# filter.net
KiCad netlist of a schematic drawn in EAGLE
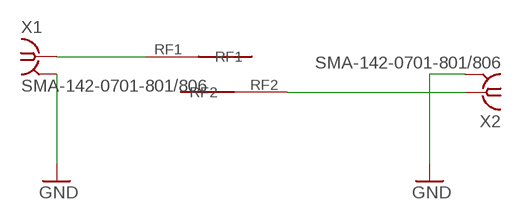
[diagram p0: schematic, sheet 1]

(export (version "E")
  (design (tool "Eeschema 10.0.6"))
  (components
    (comp (ref "U$1")
      (value "FILTER")
      (footprint "eagle-import:RF")
      (libsource (lib "eagle-import") (part "FILTER"))
    )
    (comp (ref "X1")
      (value "SMA-142-0701-801/806")
      (footprint "eagle-import:J502-ND-142-0701-801_806")
      (fields (field (name "MF") "JOHNSON COMPONENTS") (field (name "MPN") "142-0701-801"))
      (libsource (lib "eagle-import") (part "SMA-142-0701-801/806"))
    )
    (comp (ref "X2")
      (value "SMA-142-0701-801/806")
      (footprint "eagle-import:J502-ND-142-0701-801_806")
      (fields (field (name "MF") "JOHNSON COMPONENTS") (field (name "MPN") "142-0701-801"))
      (libsource (lib "eagle-import") (part "SMA-142-0701-801/806"))
    )
  )
  (nets
    (net (code "1") (name "GND") (class "Default")
      (node (ref "X1") (pin "G@1") (pinfunction "2_G@1") (pintype "passive"))
      (node (ref "X1") (pin "G@2") (pinfunction "2_G@2") (pintype "passive"))
      (node (ref "X1") (pin "G@3") (pinfunction "2_G@3") (pintype "passive"))
      (node (ref "X1") (pin "G@4") (pinfunction "2_G@4") (pintype "passive"))
      (node (ref "X2") (pin "G@1") (pinfunction "2_G@1") (pintype "passive"))
      (node (ref "X2") (pin "G@2") (pinfunction "2_G@2") (pintype "passive"))
      (node (ref "X2") (pin "G@3") (pinfunction "2_G@3") (pintype "passive"))
      (node (ref "X2") (pin "G@4") (pinfunction "2_G@4") (pintype "passive"))
    )
    (net (code "2") (name "Net-(U$1-PadRF1)") (class "Default")
      (node (ref "U$1") (pin "RF1") (pinfunction "RF1_RF1") (pintype "bidirectional"))
      (node (ref "X1") (pin "1") (pinfunction "1_1") (pintype "passive"))
    )
    (net (code "3") (name "Net-(U$1-PadRF2)") (class "Default")
      (node (ref "U$1") (pin "RF2") (pinfunction "RF2_RF2") (pintype "bidirectional"))
      (node (ref "X2") (pin "1") (pinfunction "1_1") (pintype "passive"))
    )
  )
)
